# LEDS1.net
KiCad netlist of a schematic drawn in Altium Designer
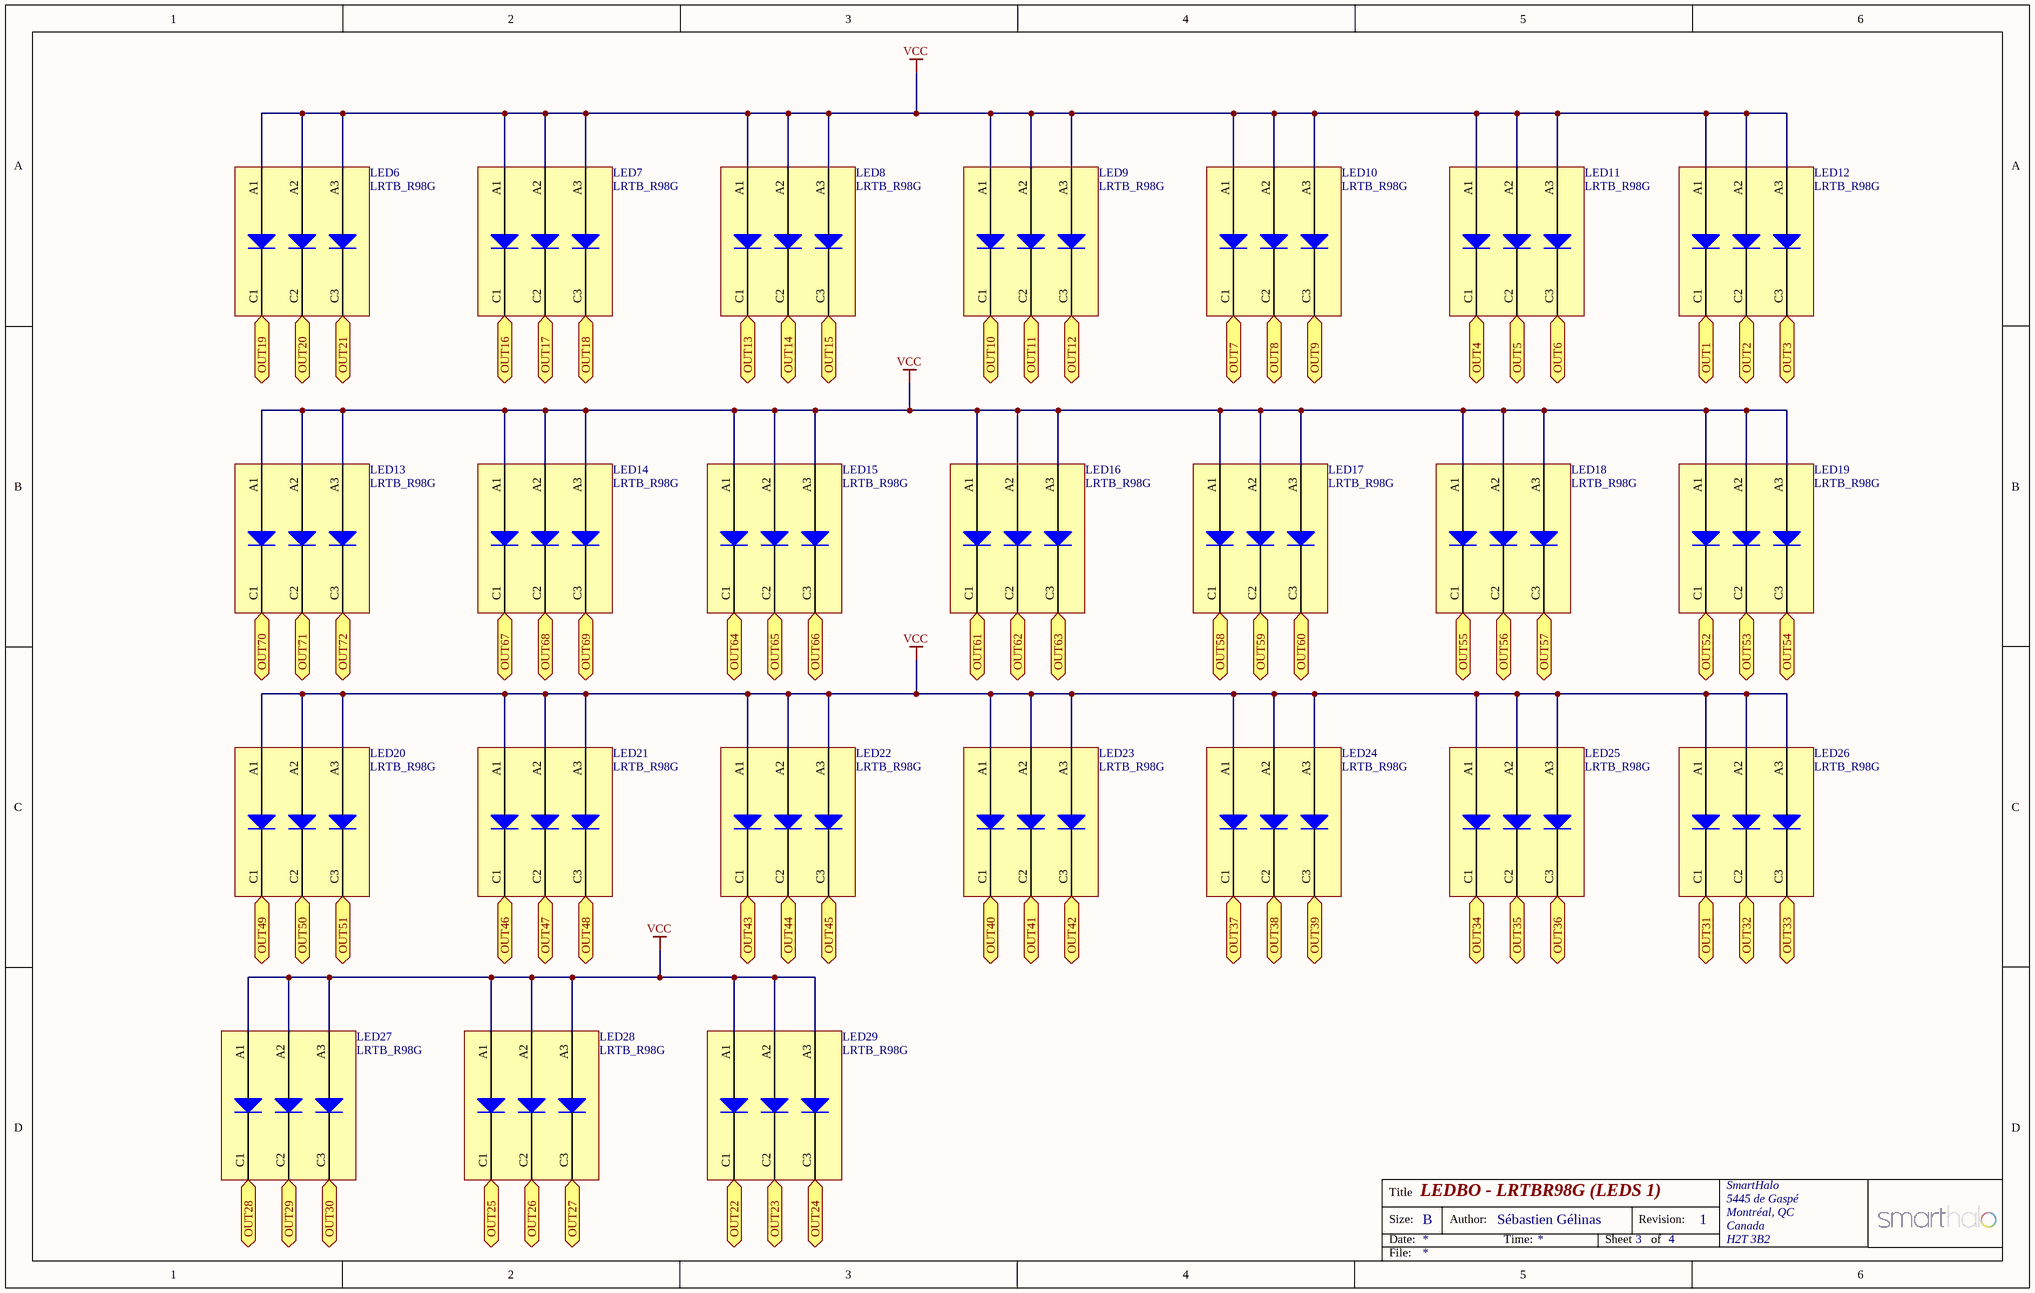
[diagram p0: LEDS1.SchDoc]

(export (version "E")
  (design (tool "Eeschema 10.0.6"))
  (components
    (comp (ref "LED6")
      (value "LRTB_R98G")
      (footprint "LRTB_R98G")
      (description "IC RGB LED OSRAM")
      (fields (field (name "MANUFACTURER") "OSRAM"))
      (libsource (lib "SmartHalo_Symbols") (part "LRTB_R98G"))
    )
    (comp (ref "LED7")
      (value "LRTB_R98G")
      (footprint "LRTB_R98G")
      (description "IC RGB LED OSRAM")
      (fields (field (name "MANUFACTURER") "OSRAM"))
      (libsource (lib "SmartHalo_Symbols") (part "LRTB_R98G"))
    )
    (comp (ref "LED8")
      (value "LRTB_R98G")
      (footprint "LRTB_R98G")
      (description "IC RGB LED OSRAM")
      (fields (field (name "MANUFACTURER") "OSRAM"))
      (libsource (lib "SmartHalo_Symbols") (part "LRTB_R98G"))
    )
    (comp (ref "LED9")
      (value "LRTB_R98G")
      (footprint "LRTB_R98G")
      (description "IC RGB LED OSRAM")
      (fields (field (name "MANUFACTURER") "OSRAM"))
      (libsource (lib "SmartHalo_Symbols") (part "LRTB_R98G"))
    )
    (comp (ref "LED10")
      (value "LRTB_R98G")
      (footprint "LRTB_R98G")
      (description "IC RGB LED OSRAM")
      (fields (field (name "MANUFACTURER") "OSRAM"))
      (libsource (lib "SmartHalo_Symbols") (part "LRTB_R98G"))
    )
    (comp (ref "LED11")
      (value "LRTB_R98G")
      (footprint "LRTB_R98G")
      (description "IC RGB LED OSRAM")
      (fields (field (name "MANUFACTURER") "OSRAM"))
      (libsource (lib "SmartHalo_Symbols") (part "LRTB_R98G"))
    )
    (comp (ref "LED12")
      (value "LRTB_R98G")
      (footprint "LRTB_R98G")
      (description "IC RGB LED OSRAM")
      (fields (field (name "MANUFACTURER") "OSRAM"))
      (libsource (lib "SmartHalo_Symbols") (part "LRTB_R98G"))
    )
    (comp (ref "LED13")
      (value "LRTB_R98G")
      (footprint "LRTB_R98G")
      (description "IC RGB LED OSRAM")
      (fields (field (name "MANUFACTURER") "OSRAM"))
      (libsource (lib "SmartHalo_Symbols") (part "LRTB_R98G"))
    )
    (comp (ref "LED14")
      (value "LRTB_R98G")
      (footprint "LRTB_R98G")
      (description "IC RGB LED OSRAM")
      (fields (field (name "MANUFACTURER") "OSRAM"))
      (libsource (lib "SmartHalo_Symbols") (part "LRTB_R98G"))
    )
    (comp (ref "LED15")
      (value "LRTB_R98G")
      (footprint "LRTB_R98G")
      (description "IC RGB LED OSRAM")
      (fields (field (name "MANUFACTURER") "OSRAM"))
      (libsource (lib "SmartHalo_Symbols") (part "LRTB_R98G"))
    )
    (comp (ref "LED16")
      (value "LRTB_R98G")
      (footprint "LRTB_R98G")
      (description "IC RGB LED OSRAM")
      (fields (field (name "MANUFACTURER") "OSRAM"))
      (libsource (lib "SmartHalo_Symbols") (part "LRTB_R98G"))
    )
    (comp (ref "LED17")
      (value "LRTB_R98G")
      (footprint "LRTB_R98G")
      (description "IC RGB LED OSRAM")
      (fields (field (name "MANUFACTURER") "OSRAM"))
      (libsource (lib "SmartHalo_Symbols") (part "LRTB_R98G"))
    )
    (comp (ref "LED18")
      (value "LRTB_R98G")
      (footprint "LRTB_R98G")
      (description "IC RGB LED OSRAM")
      (fields (field (name "MANUFACTURER") "OSRAM"))
      (libsource (lib "SmartHalo_Symbols") (part "LRTB_R98G"))
    )
    (comp (ref "LED19")
      (value "LRTB_R98G")
      (footprint "LRTB_R98G")
      (description "IC RGB LED OSRAM")
      (fields (field (name "MANUFACTURER") "OSRAM"))
      (libsource (lib "SmartHalo_Symbols") (part "LRTB_R98G"))
    )
    (comp (ref "LED20")
      (value "LRTB_R98G")
      (footprint "LRTB_R98G")
      (description "IC RGB LED OSRAM")
      (fields (field (name "MANUFACTURER") "OSRAM"))
      (libsource (lib "SmartHalo_Symbols") (part "LRTB_R98G"))
    )
    (comp (ref "LED21")
      (value "LRTB_R98G")
      (footprint "LRTB_R98G")
      (description "IC RGB LED OSRAM")
      (fields (field (name "MANUFACTURER") "OSRAM"))
      (libsource (lib "SmartHalo_Symbols") (part "LRTB_R98G"))
    )
    (comp (ref "LED22")
      (value "LRTB_R98G")
      (footprint "LRTB_R98G")
      (description "IC RGB LED OSRAM")
      (fields (field (name "MANUFACTURER") "OSRAM"))
      (libsource (lib "SmartHalo_Symbols") (part "LRTB_R98G"))
    )
    (comp (ref "LED23")
      (value "LRTB_R98G")
      (footprint "LRTB_R98G")
      (description "IC RGB LED OSRAM")
      (fields (field (name "MANUFACTURER") "OSRAM"))
      (libsource (lib "SmartHalo_Symbols") (part "LRTB_R98G"))
    )
    (comp (ref "LED24")
      (value "LRTB_R98G")
      (footprint "LRTB_R98G")
      (description "IC RGB LED OSRAM")
      (fields (field (name "MANUFACTURER") "OSRAM"))
      (libsource (lib "SmartHalo_Symbols") (part "LRTB_R98G"))
    )
    (comp (ref "LED25")
      (value "LRTB_R98G")
      (footprint "LRTB_R98G")
      (description "IC RGB LED OSRAM")
      (fields (field (name "MANUFACTURER") "OSRAM"))
      (libsource (lib "SmartHalo_Symbols") (part "LRTB_R98G"))
    )
    (comp (ref "LED26")
      (value "LRTB_R98G")
      (footprint "LRTB_R98G")
      (description "IC RGB LED OSRAM")
      (fields (field (name "MANUFACTURER") "OSRAM"))
      (libsource (lib "SmartHalo_Symbols") (part "LRTB_R98G"))
    )
    (comp (ref "LED27")
      (value "LRTB_R98G")
      (footprint "LRTB_R98G")
      (description "IC RGB LED OSRAM")
      (fields (field (name "MANUFACTURER") "OSRAM"))
      (libsource (lib "SmartHalo_Symbols") (part "LRTB_R98G"))
    )
    (comp (ref "LED28")
      (value "LRTB_R98G")
      (footprint "LRTB_R98G")
      (description "IC RGB LED OSRAM")
      (fields (field (name "MANUFACTURER") "OSRAM"))
      (libsource (lib "SmartHalo_Symbols") (part "LRTB_R98G"))
    )
    (comp (ref "LED29")
      (value "LRTB_R98G")
      (footprint "LRTB_R98G")
      (description "IC RGB LED OSRAM")
      (fields (field (name "MANUFACTURER") "OSRAM"))
      (libsource (lib "SmartHalo_Symbols") (part "LRTB_R98G"))
    )
  )
  (nets
    (net (code "1") (name "/OUT1") (class "Default")
      (node (ref "LED12") (pin "C1") (pinfunction "Cathode_Blue_C1") (pintype "passive"))
    )
    (net (code "2") (name "/OUT2") (class "Default")
      (node (ref "LED12") (pin "C2") (pinfunction "Cathode_Green_C2") (pintype "passive"))
    )
    (net (code "3") (name "/OUT3") (class "Default")
      (node (ref "LED12") (pin "C3") (pinfunction "Cathode_Red_C3") (pintype "passive"))
    )
    (net (code "4") (name "/OUT4") (class "Default")
      (node (ref "LED11") (pin "C1") (pinfunction "Cathode_Blue_C1") (pintype "passive"))
    )
    (net (code "5") (name "/OUT5") (class "Default")
      (node (ref "LED11") (pin "C2") (pinfunction "Cathode_Green_C2") (pintype "passive"))
    )
    (net (code "6") (name "/OUT6") (class "Default")
      (node (ref "LED11") (pin "C3") (pinfunction "Cathode_Red_C3") (pintype "passive"))
    )
    (net (code "7") (name "/OUT7") (class "Default")
      (node (ref "LED10") (pin "C1") (pinfunction "Cathode_Blue_C1") (pintype "passive"))
    )
    (net (code "8") (name "/OUT8") (class "Default")
      (node (ref "LED10") (pin "C2") (pinfunction "Cathode_Green_C2") (pintype "passive"))
    )
    (net (code "9") (name "/OUT9") (class "Default")
      (node (ref "LED10") (pin "C3") (pinfunction "Cathode_Red_C3") (pintype "passive"))
    )
    (net (code "10") (name "/OUT10") (class "Default")
      (node (ref "LED9") (pin "C1") (pinfunction "Cathode_Blue_C1") (pintype "passive"))
    )
    (net (code "11") (name "/OUT11") (class "Default")
      (node (ref "LED9") (pin "C2") (pinfunction "Cathode_Green_C2") (pintype "passive"))
    )
    (net (code "12") (name "/OUT12") (class "Default")
      (node (ref "LED9") (pin "C3") (pinfunction "Cathode_Red_C3") (pintype "passive"))
    )
    (net (code "13") (name "/OUT13") (class "Default")
      (node (ref "LED8") (pin "C1") (pinfunction "Cathode_Blue_C1") (pintype "passive"))
    )
    (net (code "14") (name "/OUT14") (class "Default")
      (node (ref "LED8") (pin "C2") (pinfunction "Cathode_Green_C2") (pintype "passive"))
    )
    (net (code "15") (name "/OUT15") (class "Default")
      (node (ref "LED8") (pin "C3") (pinfunction "Cathode_Red_C3") (pintype "passive"))
    )
    (net (code "16") (name "/OUT16") (class "Default")
      (node (ref "LED7") (pin "C1") (pinfunction "Cathode_Blue_C1") (pintype "passive"))
    )
    (net (code "17") (name "/OUT17") (class "Default")
      (node (ref "LED7") (pin "C2") (pinfunction "Cathode_Green_C2") (pintype "passive"))
    )
    (net (code "18") (name "/OUT18") (class "Default")
      (node (ref "LED7") (pin "C3") (pinfunction "Cathode_Red_C3") (pintype "passive"))
    )
    (net (code "19") (name "/OUT19") (class "Default")
      (node (ref "LED6") (pin "C1") (pinfunction "Cathode_Blue_C1") (pintype "passive"))
    )
    (net (code "20") (name "/OUT20") (class "Default")
      (node (ref "LED6") (pin "C2") (pinfunction "Cathode_Green_C2") (pintype "passive"))
    )
    (net (code "21") (name "/OUT21") (class "Default")
      (node (ref "LED6") (pin "C3") (pinfunction "Cathode_Red_C3") (pintype "passive"))
    )
    (net (code "22") (name "/OUT22") (class "Default")
      (node (ref "LED29") (pin "C1") (pinfunction "Cathode_Blue_C1") (pintype "passive"))
    )
    (net (code "23") (name "/OUT23") (class "Default")
      (node (ref "LED29") (pin "C2") (pinfunction "Cathode_Green_C2") (pintype "passive"))
    )
    (net (code "24") (name "/OUT24") (class "Default")
      (node (ref "LED29") (pin "C3") (pinfunction "Cathode_Red_C3") (pintype "passive"))
    )
    (net (code "25") (name "/OUT25") (class "Default")
      (node (ref "LED28") (pin "C1") (pinfunction "Cathode_Blue_C1") (pintype "passive"))
    )
    (net (code "26") (name "/OUT26") (class "Default")
      (node (ref "LED28") (pin "C2") (pinfunction "Cathode_Green_C2") (pintype "passive"))
    )
    (net (code "27") (name "/OUT27") (class "Default")
      (node (ref "LED28") (pin "C3") (pinfunction "Cathode_Red_C3") (pintype "passive"))
    )
    (net (code "28") (name "/OUT28") (class "Default")
      (node (ref "LED27") (pin "C1") (pinfunction "Cathode_Blue_C1") (pintype "passive"))
    )
    (net (code "29") (name "/OUT29") (class "Default")
      (node (ref "LED27") (pin "C2") (pinfunction "Cathode_Green_C2") (pintype "passive"))
    )
    (net (code "30") (name "/OUT30") (class "Default")
      (node (ref "LED27") (pin "C3") (pinfunction "Cathode_Red_C3") (pintype "passive"))
    )
    (net (code "31") (name "/OUT31") (class "Default")
      (node (ref "LED26") (pin "C1") (pinfunction "Cathode_Blue_C1") (pintype "passive"))
    )
    (net (code "32") (name "/OUT32") (class "Default")
      (node (ref "LED26") (pin "C2") (pinfunction "Cathode_Green_C2") (pintype "passive"))
    )
    (net (code "33") (name "/OUT33") (class "Default")
      (node (ref "LED26") (pin "C3") (pinfunction "Cathode_Red_C3") (pintype "passive"))
    )
    (net (code "34") (name "/OUT34") (class "Default")
      (node (ref "LED25") (pin "C1") (pinfunction "Cathode_Blue_C1") (pintype "passive"))
    )
    (net (code "35") (name "/OUT35") (class "Default")
      (node (ref "LED25") (pin "C2") (pinfunction "Cathode_Green_C2") (pintype "passive"))
    )
    (net (code "36") (name "/OUT36") (class "Default")
      (node (ref "LED25") (pin "C3") (pinfunction "Cathode_Red_C3") (pintype "passive"))
    )
    (net (code "37") (name "/OUT37") (class "Default")
      (node (ref "LED24") (pin "C1") (pinfunction "Cathode_Blue_C1") (pintype "passive"))
    )
    (net (code "38") (name "/OUT38") (class "Default")
      (node (ref "LED24") (pin "C2") (pinfunction "Cathode_Green_C2") (pintype "passive"))
    )
    (net (code "39") (name "/OUT39") (class "Default")
      (node (ref "LED24") (pin "C3") (pinfunction "Cathode_Red_C3") (pintype "passive"))
    )
    (net (code "40") (name "/OUT40") (class "Default")
      (node (ref "LED23") (pin "C1") (pinfunction "Cathode_Blue_C1") (pintype "passive"))
    )
    (net (code "41") (name "/OUT41") (class "Default")
      (node (ref "LED23") (pin "C2") (pinfunction "Cathode_Green_C2") (pintype "passive"))
    )
    (net (code "42") (name "/OUT42") (class "Default")
      (node (ref "LED23") (pin "C3") (pinfunction "Cathode_Red_C3") (pintype "passive"))
    )
    (net (code "43") (name "/OUT43") (class "Default")
      (node (ref "LED22") (pin "C1") (pinfunction "Cathode_Blue_C1") (pintype "passive"))
    )
    (net (code "44") (name "/OUT44") (class "Default")
      (node (ref "LED22") (pin "C2") (pinfunction "Cathode_Green_C2") (pintype "passive"))
    )
    (net (code "45") (name "/OUT45") (class "Default")
      (node (ref "LED22") (pin "C3") (pinfunction "Cathode_Red_C3") (pintype "passive"))
    )
    (net (code "46") (name "/OUT46") (class "Default")
      (node (ref "LED21") (pin "C1") (pinfunction "Cathode_Blue_C1") (pintype "passive"))
    )
    (net (code "47") (name "/OUT47") (class "Default")
      (node (ref "LED21") (pin "C2") (pinfunction "Cathode_Green_C2") (pintype "passive"))
    )
    (net (code "48") (name "/OUT48") (class "Default")
      (node (ref "LED21") (pin "C3") (pinfunction "Cathode_Red_C3") (pintype "passive"))
    )
    (net (code "49") (name "/OUT49") (class "Default")
      (node (ref "LED20") (pin "C1") (pinfunction "Cathode_Blue_C1") (pintype "passive"))
    )
    (net (code "50") (name "/OUT50") (class "Default")
      (node (ref "LED20") (pin "C2") (pinfunction "Cathode_Green_C2") (pintype "passive"))
    )
    (net (code "51") (name "/OUT51") (class "Default")
      (node (ref "LED20") (pin "C3") (pinfunction "Cathode_Red_C3") (pintype "passive"))
    )
    (net (code "52") (name "/OUT52") (class "Default")
      (node (ref "LED19") (pin "C1") (pinfunction "Cathode_Blue_C1") (pintype "passive"))
    )
    (net (code "53") (name "/OUT53") (class "Default")
      (node (ref "LED19") (pin "C2") (pinfunction "Cathode_Green_C2") (pintype "passive"))
    )
    (net (code "54") (name "/OUT54") (class "Default")
      (node (ref "LED19") (pin "C3") (pinfunction "Cathode_Red_C3") (pintype "passive"))
    )
    (net (code "55") (name "/OUT55") (class "Default")
      (node (ref "LED18") (pin "C1") (pinfunction "Cathode_Blue_C1") (pintype "passive"))
    )
    (net (code "56") (name "/OUT56") (class "Default")
      (node (ref "LED18") (pin "C2") (pinfunction "Cathode_Green_C2") (pintype "passive"))
    )
    (net (code "57") (name "/OUT57") (class "Default")
      (node (ref "LED18") (pin "C3") (pinfunction "Cathode_Red_C3") (pintype "passive"))
    )
    (net (code "58") (name "/OUT58") (class "Default")
      (node (ref "LED17") (pin "C1") (pinfunction "Cathode_Blue_C1") (pintype "passive"))
    )
    (net (code "59") (name "/OUT59") (class "Default")
      (node (ref "LED17") (pin "C2") (pinfunction "Cathode_Green_C2") (pintype "passive"))
    )
    (net (code "60") (name "/OUT60") (class "Default")
      (node (ref "LED17") (pin "C3") (pinfunction "Cathode_Red_C3") (pintype "passive"))
    )
    (net (code "61") (name "/OUT61") (class "Default")
      (node (ref "LED16") (pin "C1") (pinfunction "Cathode_Blue_C1") (pintype "passive"))
    )
    (net (code "62") (name "/OUT62") (class "Default")
      (node (ref "LED16") (pin "C2") (pinfunction "Cathode_Green_C2") (pintype "passive"))
    )
    (net (code "63") (name "/OUT63") (class "Default")
      (node (ref "LED16") (pin "C3") (pinfunction "Cathode_Red_C3") (pintype "passive"))
    )
    (net (code "64") (name "/OUT64") (class "Default")
      (node (ref "LED15") (pin "C1") (pinfunction "Cathode_Blue_C1") (pintype "passive"))
    )
    (net (code "65") (name "/OUT65") (class "Default")
      (node (ref "LED15") (pin "C2") (pinfunction "Cathode_Green_C2") (pintype "passive"))
    )
    (net (code "66") (name "/OUT66") (class "Default")
      (node (ref "LED15") (pin "C3") (pinfunction "Cathode_Red_C3") (pintype "passive"))
    )
    (net (code "67") (name "/OUT67") (class "Default")
      (node (ref "LED14") (pin "C1") (pinfunction "Cathode_Blue_C1") (pintype "passive"))
    )
    (net (code "68") (name "/OUT68") (class "Default")
      (node (ref "LED14") (pin "C2") (pinfunction "Cathode_Green_C2") (pintype "passive"))
    )
    (net (code "69") (name "/OUT69") (class "Default")
      (node (ref "LED14") (pin "C3") (pinfunction "Cathode_Red_C3") (pintype "passive"))
    )
    (net (code "70") (name "/OUT70") (class "Default")
      (node (ref "LED13") (pin "C1") (pinfunction "Cathode_Blue_C1") (pintype "passive"))
    )
    (net (code "71") (name "/OUT71") (class "Default")
      (node (ref "LED13") (pin "C2") (pinfunction "Cathode_Green_C2") (pintype "passive"))
    )
    (net (code "72") (name "/OUT72") (class "Default")
      (node (ref "LED13") (pin "C3") (pinfunction "Cathode_Red_C3") (pintype "passive"))
    )
    (net (code "73") (name "VCC") (class "Default")
      (node (ref "LED10") (pin "A1") (pinfunction "Anode_Blue_A1") (pintype "passive"))
      (node (ref "LED10") (pin "A2") (pinfunction "Anode_Green_A2") (pintype "passive"))
      (node (ref "LED10") (pin "A3") (pinfunction "Anode_Red_A3") (pintype "passive"))
      (node (ref "LED11") (pin "A1") (pinfunction "Anode_Blue_A1") (pintype "passive"))
      (node (ref "LED11") (pin "A2") (pinfunction "Anode_Green_A2") (pintype "passive"))
      (node (ref "LED11") (pin "A3") (pinfunction "Anode_Red_A3") (pintype "passive"))
      (node (ref "LED12") (pin "A1") (pinfunction "Anode_Blue_A1") (pintype "passive"))
      (node (ref "LED12") (pin "A2") (pinfunction "Anode_Green_A2") (pintype "passive"))
      (node (ref "LED12") (pin "A3") (pinfunction "Anode_Red_A3") (pintype "passive"))
      (node (ref "LED13") (pin "A1") (pinfunction "Anode_Blue_A1") (pintype "passive"))
      (node (ref "LED13") (pin "A2") (pinfunction "Anode_Green_A2") (pintype "passive"))
      (node (ref "LED13") (pin "A3") (pinfunction "Anode_Red_A3") (pintype "passive"))
      (node (ref "LED14") (pin "A1") (pinfunction "Anode_Blue_A1") (pintype "passive"))
      (node (ref "LED14") (pin "A2") (pinfunction "Anode_Green_A2") (pintype "passive"))
      (node (ref "LED14") (pin "A3") (pinfunction "Anode_Red_A3") (pintype "passive"))
      (node (ref "LED15") (pin "A1") (pinfunction "Anode_Blue_A1") (pintype "passive"))
      (node (ref "LED15") (pin "A2") (pinfunction "Anode_Green_A2") (pintype "passive"))
      (node (ref "LED15") (pin "A3") (pinfunction "Anode_Red_A3") (pintype "passive"))
      (node (ref "LED16") (pin "A1") (pinfunction "Anode_Blue_A1") (pintype "passive"))
      (node (ref "LED16") (pin "A2") (pinfunction "Anode_Green_A2") (pintype "passive"))
      (node (ref "LED16") (pin "A3") (pinfunction "Anode_Red_A3") (pintype "passive"))
      (node (ref "LED17") (pin "A1") (pinfunction "Anode_Blue_A1") (pintype "passive"))
      (node (ref "LED17") (pin "A2") (pinfunction "Anode_Green_A2") (pintype "passive"))
      (node (ref "LED17") (pin "A3") (pinfunction "Anode_Red_A3") (pintype "passive"))
      (node (ref "LED18") (pin "A1") (pinfunction "Anode_Blue_A1") (pintype "passive"))
      (node (ref "LED18") (pin "A2") (pinfunction "Anode_Green_A2") (pintype "passive"))
      (node (ref "LED18") (pin "A3") (pinfunction "Anode_Red_A3") (pintype "passive"))
      (node (ref "LED19") (pin "A1") (pinfunction "Anode_Blue_A1") (pintype "passive"))
      (node (ref "LED19") (pin "A2") (pinfunction "Anode_Green_A2") (pintype "passive"))
      (node (ref "LED19") (pin "A3") (pinfunction "Anode_Red_A3") (pintype "passive"))
      (node (ref "LED20") (pin "A1") (pinfunction "Anode_Blue_A1") (pintype "passive"))
      (node (ref "LED20") (pin "A2") (pinfunction "Anode_Green_A2") (pintype "passive"))
      (node (ref "LED20") (pin "A3") (pinfunction "Anode_Red_A3") (pintype "passive"))
      (node (ref "LED21") (pin "A1") (pinfunction "Anode_Blue_A1") (pintype "passive"))
      (node (ref "LED21") (pin "A2") (pinfunction "Anode_Green_A2") (pintype "passive"))
      (node (ref "LED21") (pin "A3") (pinfunction "Anode_Red_A3") (pintype "passive"))
      (node (ref "LED22") (pin "A1") (pinfunction "Anode_Blue_A1") (pintype "passive"))
      (node (ref "LED22") (pin "A2") (pinfunction "Anode_Green_A2") (pintype "passive"))
      (node (ref "LED22") (pin "A3") (pinfunction "Anode_Red_A3") (pintype "passive"))
      (node (ref "LED23") (pin "A1") (pinfunction "Anode_Blue_A1") (pintype "passive"))
      (node (ref "LED23") (pin "A2") (pinfunction "Anode_Green_A2") (pintype "passive"))
      (node (ref "LED23") (pin "A3") (pinfunction "Anode_Red_A3") (pintype "passive"))
      (node (ref "LED24") (pin "A1") (pinfunction "Anode_Blue_A1") (pintype "passive"))
      (node (ref "LED24") (pin "A2") (pinfunction "Anode_Green_A2") (pintype "passive"))
      (node (ref "LED24") (pin "A3") (pinfunction "Anode_Red_A3") (pintype "passive"))
      (node (ref "LED25") (pin "A1") (pinfunction "Anode_Blue_A1") (pintype "passive"))
      (node (ref "LED25") (pin "A2") (pinfunction "Anode_Green_A2") (pintype "passive"))
      (node (ref "LED25") (pin "A3") (pinfunction "Anode_Red_A3") (pintype "passive"))
      (node (ref "LED26") (pin "A1") (pinfunction "Anode_Blue_A1") (pintype "passive"))
      (node (ref "LED26") (pin "A2") (pinfunction "Anode_Green_A2") (pintype "passive"))
      (node (ref "LED26") (pin "A3") (pinfunction "Anode_Red_A3") (pintype "passive"))
      (node (ref "LED27") (pin "A1") (pinfunction "Anode_Blue_A1") (pintype "passive"))
      (node (ref "LED27") (pin "A2") (pinfunction "Anode_Green_A2") (pintype "passive"))
      (node (ref "LED27") (pin "A3") (pinfunction "Anode_Red_A3") (pintype "passive"))
      (node (ref "LED28") (pin "A1") (pinfunction "Anode_Blue_A1") (pintype "passive"))
      (node (ref "LED28") (pin "A2") (pinfunction "Anode_Green_A2") (pintype "passive"))
      (node (ref "LED28") (pin "A3") (pinfunction "Anode_Red_A3") (pintype "passive"))
      (node (ref "LED29") (pin "A1") (pinfunction "Anode_Blue_A1") (pintype "passive"))
      (node (ref "LED29") (pin "A2") (pinfunction "Anode_Green_A2") (pintype "passive"))
      (node (ref "LED29") (pin "A3") (pinfunction "Anode_Red_A3") (pintype "passive"))
      (node (ref "LED6") (pin "A1") (pinfunction "Anode_Blue_A1") (pintype "passive"))
      (node (ref "LED6") (pin "A2") (pinfunction "Anode_Green_A2") (pintype "passive"))
      (node (ref "LED6") (pin "A3") (pinfunction "Anode_Red_A3") (pintype "passive"))
      (node (ref "LED7") (pin "A1") (pinfunction "Anode_Blue_A1") (pintype "passive"))
      (node (ref "LED7") (pin "A2") (pinfunction "Anode_Green_A2") (pintype "passive"))
      (node (ref "LED7") (pin "A3") (pinfunction "Anode_Red_A3") (pintype "passive"))
      (node (ref "LED8") (pin "A1") (pinfunction "Anode_Blue_A1") (pintype "passive"))
      (node (ref "LED8") (pin "A2") (pinfunction "Anode_Green_A2") (pintype "passive"))
      (node (ref "LED8") (pin "A3") (pinfunction "Anode_Red_A3") (pintype "passive"))
      (node (ref "LED9") (pin "A1") (pinfunction "Anode_Blue_A1") (pintype "passive"))
      (node (ref "LED9") (pin "A2") (pinfunction "Anode_Green_A2") (pintype "passive"))
      (node (ref "LED9") (pin "A3") (pinfunction "Anode_Red_A3") (pintype "passive"))
    )
  )
)
